# VIC20_HypExp.net
KiCad netlist of a schematic drawn in EAGLE
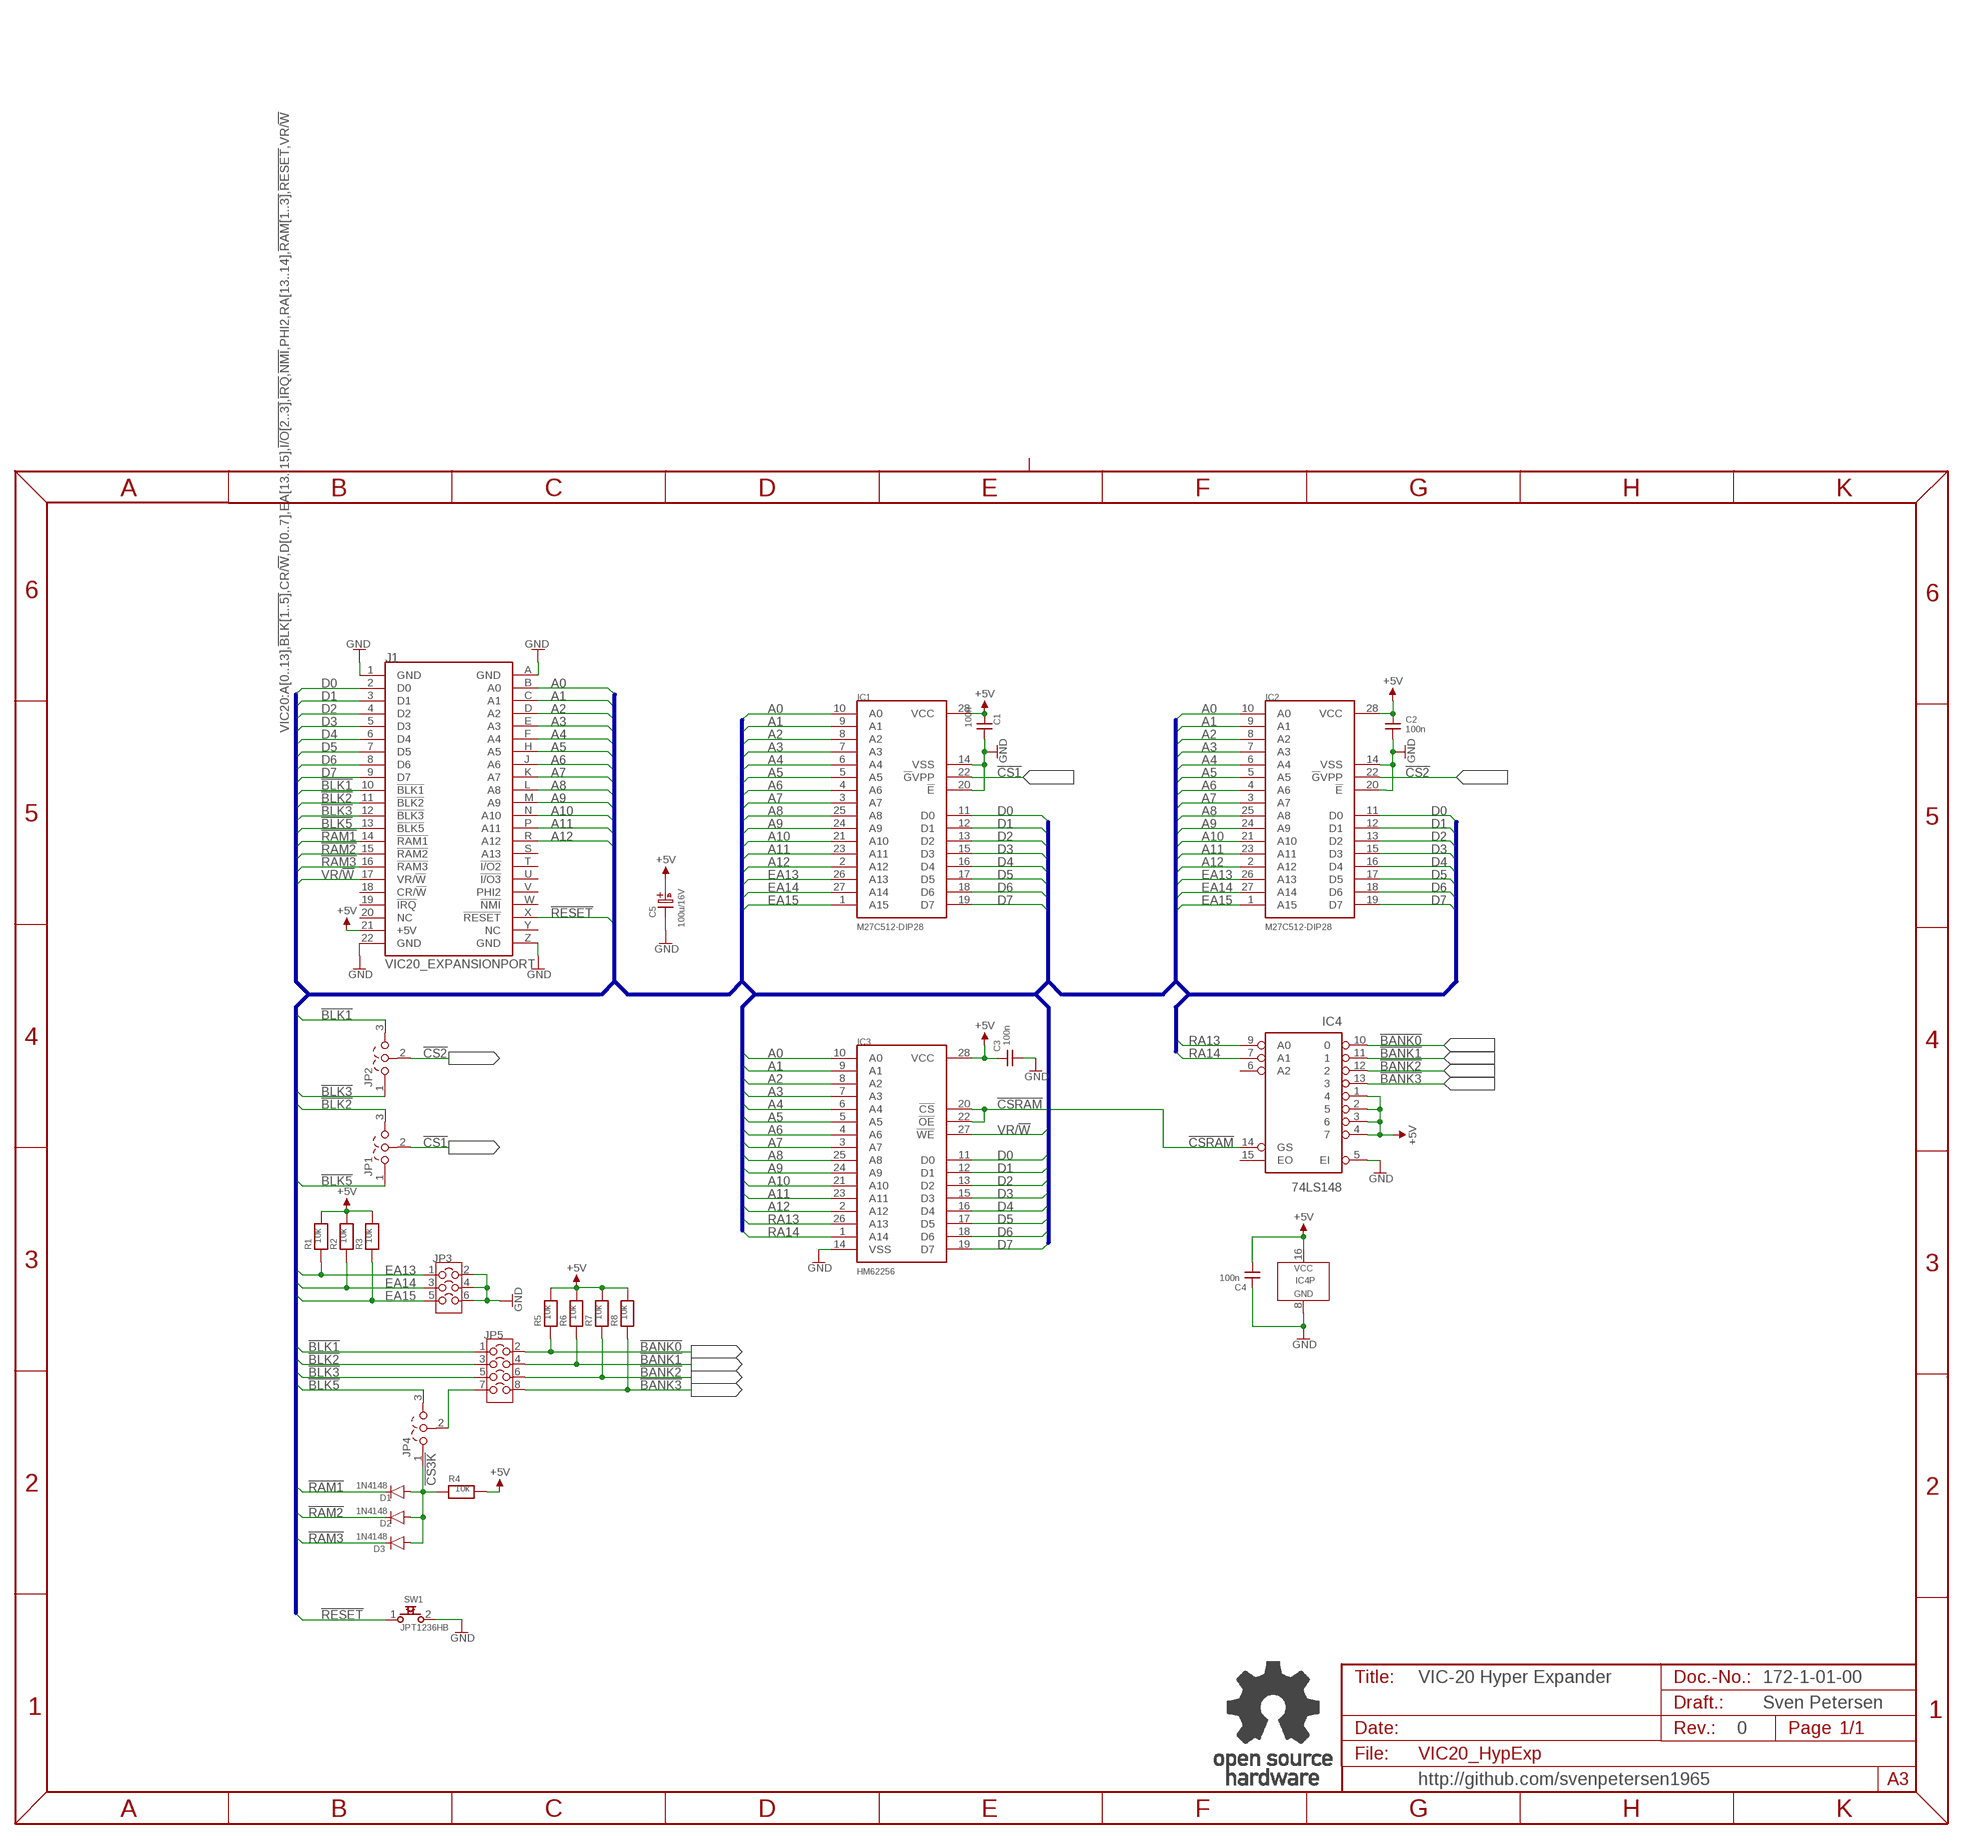
[diagram p0: schematic, sheet 1]

(export (version "E")
  (design (tool "Eeschema 10.0.6"))
  (components
    (comp (ref "C1")
      (value "100n")
      (footprint "eagle-import:C-2,5")
      (libsource (lib "eagle-import") (part "CAP01"))
    )
    (comp (ref "C2")
      (value "100n")
      (footprint "eagle-import:C-2,5")
      (libsource (lib "eagle-import") (part "CAP01"))
    )
    (comp (ref "C3")
      (value "100n")
      (footprint "eagle-import:C-2,5")
      (libsource (lib "eagle-import") (part "CAP01"))
    )
    (comp (ref "C4")
      (value "100n")
      (footprint "eagle-import:C-2,5")
      (libsource (lib "eagle-import") (part "CAP01"))
    )
    (comp (ref "C5")
      (value "100u/16V")
      (footprint "eagle-import:C07_2,5")
      (libsource (lib "eagle-import") (part "C07/2,5"))
    )
    (comp (ref "D1")
      (value "1N4148")
      (footprint "eagle-import:DO-35_3")
      (libsource (lib "eagle-import") (part "1N41480.3{dblquote}"))
    )
    (comp (ref "D2")
      (value "1N4148")
      (footprint "eagle-import:DO-35_3")
      (libsource (lib "eagle-import") (part "1N41480.3{dblquote}"))
    )
    (comp (ref "D3")
      (value "1N4148")
      (footprint "eagle-import:DO-35_3")
      (libsource (lib "eagle-import") (part "1N41480.3{dblquote}"))
    )
    (comp (ref "IC1")
      (value "M27C512-DIP28")
      (footprint "eagle-import:DIL28-6")
      (libsource (lib "eagle-import") (part "M27C512-DIP28"))
    )
    (comp (ref "IC2")
      (value "M27C512-DIP28")
      (footprint "eagle-import:DIL28-6")
      (libsource (lib "eagle-import") (part "M27C512-DIP28"))
    )
    (comp (ref "IC3")
      (value "HM62256")
      (footprint "eagle-import:DIL28-6")
      (libsource (lib "eagle-import") (part "HM62256"))
    )
    (comp (ref "IC4")
      (value "74LS148")
      (footprint "eagle-import:DIL-16")
      (libsource (lib "eagle-import") (part "74148DIL"))
    )
    (comp (ref "J1")
      (value "VIC20_EXPANSIONPORT")
      (footprint "eagle-import:VIC20_EXPANSION")
      (libsource (lib "eagle-import") (part "VIC20_EXPANSIONPORT"))
    )
    (comp (ref "JP1")
      (value "COMBI-3P")
      (footprint "eagle-import:COMBI-3P")
      (libsource (lib "eagle-import") (part "COMBI-3P"))
    )
    (comp (ref "JP2")
      (value "COMBI-3P")
      (footprint "eagle-import:COMBI-3P")
      (libsource (lib "eagle-import") (part "COMBI-3P"))
    )
    (comp (ref "JP3")
      (value "COMBI-3X2P")
      (footprint "eagle-import:COMBI-3X2")
      (libsource (lib "eagle-import") (part "COMBI-3X2P"))
    )
    (comp (ref "JP4")
      (value "COMBI-3P")
      (footprint "eagle-import:COMBI-3P")
      (libsource (lib "eagle-import") (part "COMBI-3P"))
    )
    (comp (ref "JP5")
      (value "COMBI-4X2P")
      (footprint "eagle-import:COMBI-4X2")
      (libsource (lib "eagle-import") (part "COMBI-4X2P"))
    )
    (comp (ref "R1")
      (value "10k")
      (footprint "eagle-import:R-10")
      (libsource (lib "eagle-import") (part "RES04"))
    )
    (comp (ref "R2")
      (value "10k")
      (footprint "eagle-import:R-10")
      (libsource (lib "eagle-import") (part "RES04"))
    )
    (comp (ref "R3")
      (value "10k")
      (footprint "eagle-import:R-10")
      (libsource (lib "eagle-import") (part "RES04"))
    )
    (comp (ref "R4")
      (value "10k")
      (footprint "eagle-import:R-10")
      (libsource (lib "eagle-import") (part "RES04"))
    )
    (comp (ref "R5")
      (value "10k")
      (footprint "eagle-import:R-10")
      (libsource (lib "eagle-import") (part "RES04"))
    )
    (comp (ref "R6")
      (value "10k")
      (footprint "eagle-import:R-10")
      (libsource (lib "eagle-import") (part "RES04"))
    )
    (comp (ref "R7")
      (value "10k")
      (footprint "eagle-import:R-10")
      (libsource (lib "eagle-import") (part "RES04"))
    )
    (comp (ref "R8")
      (value "10k")
      (footprint "eagle-import:R-10")
      (libsource (lib "eagle-import") (part "RES04"))
    )
    (comp (ref "SW1")
      (value "JPT1236HB")
      (footprint "eagle-import:JTP_1236HB")
      (libsource (lib "eagle-import") (part "JPT1236HB"))
    )
    (comp (ref "U$2")
      (value "OPEN_SOURCE_HW")
      (footprint "eagle-import:OPENHW")
      (libsource (lib "eagle-import") (part "OPEN_SOURCE_HW"))
    )
  )
  (nets
    (net (code "5") (name "+5V") (class "Default")
      (node (ref "C1") (pin "1") (pinfunction "1_1") (pintype "passive"))
      (node (ref "C2") (pin "1") (pinfunction "1_1") (pintype "passive"))
      (node (ref "C3") (pin "2") (pinfunction "2_2") (pintype "passive"))
      (node (ref "C4") (pin "1") (pinfunction "1_1") (pintype "passive"))
      (node (ref "C5") (pin "A") (pinfunction "+_A") (pintype "passive"))
      (node (ref "IC1") (pin "28") (pinfunction "VCC_28") (pintype "power_in"))
      (node (ref "IC2") (pin "28") (pinfunction "VCC_28") (pintype "power_in"))
      (node (ref "IC3") (pin "28") (pinfunction "VCC_28") (pintype "power_in"))
      (node (ref "IC4") (pin "1") (pinfunction "4_1") (pintype "input"))
      (node (ref "IC4") (pin "16") (pinfunction "VCC_16") (pintype "bidirectional"))
      (node (ref "IC4") (pin "2") (pinfunction "5_2") (pintype "input"))
      (node (ref "IC4") (pin "3") (pinfunction "6_3") (pintype "input"))
      (node (ref "IC4") (pin "4") (pinfunction "7_4") (pintype "input"))
      (node (ref "J1") (pin "21") (pinfunction "+5V_21") (pintype "power_in"))
      (node (ref "R1") (pin "2") (pinfunction "2_2") (pintype "passive"))
      (node (ref "R2") (pin "2") (pinfunction "2_2") (pintype "passive"))
      (node (ref "R3") (pin "2") (pinfunction "2_2") (pintype "passive"))
      (node (ref "R4") (pin "2") (pinfunction "2_2") (pintype "passive"))
      (node (ref "R5") (pin "2") (pinfunction "2_2") (pintype "passive"))
      (node (ref "R6") (pin "2") (pinfunction "2_2") (pintype "passive"))
      (node (ref "R7") (pin "2") (pinfunction "2_2") (pintype "passive"))
      (node (ref "R8") (pin "2") (pinfunction "2_2") (pintype "passive"))
    )
    (net (code "6") (name "/A0") (class "Default")
      (node (ref "IC1") (pin "10") (pinfunction "A0_10") (pintype "input"))
      (node (ref "IC2") (pin "10") (pinfunction "A0_10") (pintype "input"))
      (node (ref "IC3") (pin "10") (pinfunction "A0_10") (pintype "input"))
      (node (ref "J1") (pin "B") (pinfunction "A0_B") (pintype "bidirectional"))
    )
    (net (code "7") (name "/A1") (class "Default")
      (node (ref "IC1") (pin "9") (pinfunction "A1_9") (pintype "input"))
      (node (ref "IC2") (pin "9") (pinfunction "A1_9") (pintype "input"))
      (node (ref "IC3") (pin "9") (pinfunction "A1_9") (pintype "input"))
      (node (ref "J1") (pin "C") (pinfunction "A1_C") (pintype "bidirectional"))
    )
    (net (code "8") (name "/A2") (class "Default")
      (node (ref "IC1") (pin "8") (pinfunction "A2_8") (pintype "input"))
      (node (ref "IC2") (pin "8") (pinfunction "A2_8") (pintype "input"))
      (node (ref "IC3") (pin "8") (pinfunction "A2_8") (pintype "input"))
      (node (ref "J1") (pin "D") (pinfunction "A2_D") (pintype "bidirectional"))
    )
    (net (code "9") (name "/A3") (class "Default")
      (node (ref "IC1") (pin "7") (pinfunction "A3_7") (pintype "input"))
      (node (ref "IC2") (pin "7") (pinfunction "A3_7") (pintype "input"))
      (node (ref "IC3") (pin "7") (pinfunction "A3_7") (pintype "input"))
      (node (ref "J1") (pin "E") (pinfunction "A3_E") (pintype "bidirectional"))
    )
    (net (code "10") (name "/A4") (class "Default")
      (node (ref "IC1") (pin "6") (pinfunction "A4_6") (pintype "input"))
      (node (ref "IC2") (pin "6") (pinfunction "A4_6") (pintype "input"))
      (node (ref "IC3") (pin "6") (pinfunction "A4_6") (pintype "input"))
      (node (ref "J1") (pin "F") (pinfunction "A4_F") (pintype "bidirectional"))
    )
    (net (code "11") (name "/A5") (class "Default")
      (node (ref "IC1") (pin "5") (pinfunction "A5_5") (pintype "input"))
      (node (ref "IC2") (pin "5") (pinfunction "A5_5") (pintype "input"))
      (node (ref "IC3") (pin "5") (pinfunction "A5_5") (pintype "input"))
      (node (ref "J1") (pin "H") (pinfunction "A5_H") (pintype "bidirectional"))
    )
    (net (code "12") (name "/A6") (class "Default")
      (node (ref "IC1") (pin "4") (pinfunction "A6_4") (pintype "input"))
      (node (ref "IC2") (pin "4") (pinfunction "A6_4") (pintype "input"))
      (node (ref "IC3") (pin "4") (pinfunction "A6_4") (pintype "input"))
      (node (ref "J1") (pin "J") (pinfunction "A6_J") (pintype "bidirectional"))
    )
    (net (code "13") (name "/A7") (class "Default")
      (node (ref "IC1") (pin "3") (pinfunction "A7_3") (pintype "input"))
      (node (ref "IC2") (pin "3") (pinfunction "A7_3") (pintype "input"))
      (node (ref "IC3") (pin "3") (pinfunction "A7_3") (pintype "input"))
      (node (ref "J1") (pin "K") (pinfunction "A7_K") (pintype "bidirectional"))
    )
    (net (code "14") (name "/A8") (class "Default")
      (node (ref "IC1") (pin "25") (pinfunction "A8_25") (pintype "input"))
      (node (ref "IC2") (pin "25") (pinfunction "A8_25") (pintype "input"))
      (node (ref "IC3") (pin "25") (pinfunction "A8_25") (pintype "input"))
      (node (ref "J1") (pin "L") (pinfunction "A8_L") (pintype "bidirectional"))
    )
    (net (code "15") (name "/A9") (class "Default")
      (node (ref "IC1") (pin "24") (pinfunction "A9_24") (pintype "input"))
      (node (ref "IC2") (pin "24") (pinfunction "A9_24") (pintype "input"))
      (node (ref "IC3") (pin "24") (pinfunction "A9_24") (pintype "input"))
      (node (ref "J1") (pin "M") (pinfunction "A9_M") (pintype "bidirectional"))
    )
    (net (code "16") (name "/A10") (class "Default")
      (node (ref "IC1") (pin "21") (pinfunction "A10_21") (pintype "input"))
      (node (ref "IC2") (pin "21") (pinfunction "A10_21") (pintype "input"))
      (node (ref "IC3") (pin "21") (pinfunction "A10_21") (pintype "input"))
      (node (ref "J1") (pin "N") (pinfunction "A10_N") (pintype "bidirectional"))
    )
    (net (code "17") (name "/A11") (class "Default")
      (node (ref "IC1") (pin "23") (pinfunction "A11_23") (pintype "input"))
      (node (ref "IC2") (pin "23") (pinfunction "A11_23") (pintype "input"))
      (node (ref "IC3") (pin "23") (pinfunction "A11_23") (pintype "input"))
      (node (ref "J1") (pin "P") (pinfunction "A11_P") (pintype "bidirectional"))
    )
    (net (code "18") (name "/A12") (class "Default")
      (node (ref "IC1") (pin "2") (pinfunction "A12_2") (pintype "input"))
      (node (ref "IC2") (pin "2") (pinfunction "A12_2") (pintype "input"))
      (node (ref "IC3") (pin "2") (pinfunction "A12_2") (pintype "input"))
      (node (ref "J1") (pin "R") (pinfunction "A12_R") (pintype "bidirectional"))
    )
    (net (code "19") (name "/D0") (class "Default")
      (node (ref "IC1") (pin "11") (pinfunction "D0_11") (pintype "bidirectional"))
      (node (ref "IC2") (pin "11") (pinfunction "D0_11") (pintype "bidirectional"))
      (node (ref "IC3") (pin "11") (pinfunction "D0_11") (pintype "bidirectional"))
      (node (ref "J1") (pin "2") (pinfunction "D0_2") (pintype "bidirectional"))
    )
    (net (code "20") (name "/D1") (class "Default")
      (node (ref "IC1") (pin "12") (pinfunction "D1_12") (pintype "bidirectional"))
      (node (ref "IC2") (pin "12") (pinfunction "D1_12") (pintype "bidirectional"))
      (node (ref "IC3") (pin "12") (pinfunction "D1_12") (pintype "bidirectional"))
      (node (ref "J1") (pin "3") (pinfunction "D1_3") (pintype "bidirectional"))
    )
    (net (code "21") (name "/D2") (class "Default")
      (node (ref "IC1") (pin "13") (pinfunction "D2_13") (pintype "bidirectional"))
      (node (ref "IC2") (pin "13") (pinfunction "D2_13") (pintype "bidirectional"))
      (node (ref "IC3") (pin "13") (pinfunction "D2_13") (pintype "bidirectional"))
      (node (ref "J1") (pin "4") (pinfunction "D2_4") (pintype "bidirectional"))
    )
    (net (code "22") (name "/D3") (class "Default")
      (node (ref "IC1") (pin "15") (pinfunction "D3_15") (pintype "bidirectional"))
      (node (ref "IC2") (pin "15") (pinfunction "D3_15") (pintype "bidirectional"))
      (node (ref "IC3") (pin "15") (pinfunction "D3_15") (pintype "bidirectional"))
      (node (ref "J1") (pin "5") (pinfunction "D3_5") (pintype "bidirectional"))
    )
    (net (code "23") (name "/D4") (class "Default")
      (node (ref "IC1") (pin "16") (pinfunction "D4_16") (pintype "bidirectional"))
      (node (ref "IC2") (pin "16") (pinfunction "D4_16") (pintype "bidirectional"))
      (node (ref "IC3") (pin "16") (pinfunction "D4_16") (pintype "bidirectional"))
      (node (ref "J1") (pin "6") (pinfunction "D4_6") (pintype "bidirectional"))
    )
    (net (code "24") (name "/D5") (class "Default")
      (node (ref "IC1") (pin "17") (pinfunction "D5_17") (pintype "bidirectional"))
      (node (ref "IC2") (pin "17") (pinfunction "D5_17") (pintype "bidirectional"))
      (node (ref "IC3") (pin "17") (pinfunction "D5_17") (pintype "bidirectional"))
      (node (ref "J1") (pin "7") (pinfunction "D5_7") (pintype "bidirectional"))
    )
    (net (code "25") (name "/D6") (class "Default")
      (node (ref "IC1") (pin "18") (pinfunction "D6_18") (pintype "bidirectional"))
      (node (ref "IC2") (pin "18") (pinfunction "D6_18") (pintype "bidirectional"))
      (node (ref "IC3") (pin "18") (pinfunction "D6_18") (pintype "bidirectional"))
      (node (ref "J1") (pin "8") (pinfunction "D6_8") (pintype "bidirectional"))
    )
    (net (code "26") (name "/D7") (class "Default")
      (node (ref "IC1") (pin "19") (pinfunction "D7_19") (pintype "bidirectional"))
      (node (ref "IC2") (pin "19") (pinfunction "D7_19") (pintype "bidirectional"))
      (node (ref "IC3") (pin "19") (pinfunction "D7_19") (pintype "bidirectional"))
      (node (ref "J1") (pin "9") (pinfunction "D7_9") (pintype "bidirectional"))
    )
    (net (code "27") (name "/EA13") (class "Default")
      (node (ref "IC1") (pin "26") (pinfunction "A13_26") (pintype "input"))
      (node (ref "IC2") (pin "26") (pinfunction "A13_26") (pintype "input"))
      (node (ref "JP3") (pin "1") (pinfunction "1_1") (pintype "bidirectional"))
      (node (ref "R1") (pin "1") (pinfunction "1_1") (pintype "passive"))
    )
    (net (code "28") (name "/EA14") (class "Default")
      (node (ref "IC1") (pin "27") (pinfunction "A14_27") (pintype "input"))
      (node (ref "IC2") (pin "27") (pinfunction "A14_27") (pintype "input"))
      (node (ref "JP3") (pin "3") (pinfunction "3_3") (pintype "bidirectional"))
      (node (ref "R2") (pin "1") (pinfunction "1_1") (pintype "passive"))
    )
    (net (code "29") (name "/EA15") (class "Default")
      (node (ref "IC1") (pin "1") (pinfunction "A15_1") (pintype "input"))
      (node (ref "IC2") (pin "1") (pinfunction "A15_1") (pintype "input"))
      (node (ref "JP3") (pin "5") (pinfunction "5_5") (pintype "bidirectional"))
      (node (ref "R3") (pin "1") (pinfunction "1_1") (pintype "passive"))
    )
    (net (code "30") (name "/NC") (class "Default")
      (node (ref "J1") (pin "20") (pinfunction "NC_20") (pintype "power_in"))
    )
    (net (code "31") (name "/RA13") (class "Default")
      (node (ref "IC3") (pin "26") (pinfunction "A13_26") (pintype "input"))
      (node (ref "IC4") (pin "9") (pinfunction "A0_9") (pintype "output"))
    )
    (net (code "32") (name "/RA14") (class "Default")
      (node (ref "IC3") (pin "1") (pinfunction "A14_1") (pintype "input"))
      (node (ref "IC4") (pin "7") (pinfunction "A1_7") (pintype "output"))
    )
    (net (code "33") (name "/VR{slash}~{W}") (class "Default")
      (node (ref "IC3") (pin "27") (pinfunction "~{WE}_27") (pintype "input"))
      (node (ref "J1") (pin "17") (pinfunction "VR/~{W}_17") (pintype "output"))
    )
    (net (code "35") (name "/~{BANK0}") (class "Default")
      (node (ref "IC4") (pin "10") (pinfunction "0_10") (pintype "input"))
      (node (ref "JP5") (pin "2") (pinfunction "2_2") (pintype "bidirectional"))
      (node (ref "R5") (pin "1") (pinfunction "1_1") (pintype "passive"))
    )
    (net (code "36") (name "/~{BANK1}") (class "Default")
      (node (ref "IC4") (pin "11") (pinfunction "1_11") (pintype "input"))
      (node (ref "JP5") (pin "4") (pinfunction "4_4") (pintype "bidirectional"))
      (node (ref "R6") (pin "1") (pinfunction "1_1") (pintype "passive"))
    )
    (net (code "37") (name "/~{BANK2}") (class "Default")
      (node (ref "IC4") (pin "12") (pinfunction "2_12") (pintype "input"))
      (node (ref "JP5") (pin "6") (pinfunction "6_6") (pintype "bidirectional"))
      (node (ref "R7") (pin "1") (pinfunction "1_1") (pintype "passive"))
    )
    (net (code "38") (name "/~{BANK3}") (class "Default")
      (node (ref "IC4") (pin "13") (pinfunction "3_13") (pintype "input"))
      (node (ref "JP5") (pin "8") (pinfunction "8_8") (pintype "bidirectional"))
      (node (ref "R8") (pin "1") (pinfunction "1_1") (pintype "passive"))
    )
    (net (code "39") (name "/~{BLK1}") (class "Default")
      (node (ref "J1") (pin "10") (pinfunction "~{BLK1}_10") (pintype "input"))
      (node (ref "JP2") (pin "3") (pinfunction "3_3") (pintype "bidirectional"))
      (node (ref "JP5") (pin "1") (pinfunction "1_1") (pintype "bidirectional"))
    )
    (net (code "40") (name "/~{BLK2}") (class "Default")
      (node (ref "J1") (pin "11") (pinfunction "~{BLK2}_11") (pintype "input"))
      (node (ref "JP1") (pin "3") (pinfunction "3_3") (pintype "bidirectional"))
      (node (ref "JP5") (pin "3") (pinfunction "3_3") (pintype "bidirectional"))
    )
    (net (code "41") (name "/~{BLK3}") (class "Default")
      (node (ref "J1") (pin "12") (pinfunction "~{BLK3}_12") (pintype "output"))
      (node (ref "JP2") (pin "1") (pinfunction "1_1") (pintype "bidirectional"))
      (node (ref "JP5") (pin "5") (pinfunction "5_5") (pintype "bidirectional"))
    )
    (net (code "42") (name "/~{BLK5}") (class "Default")
      (node (ref "J1") (pin "13") (pinfunction "~{BLK5}_13") (pintype "output"))
      (node (ref "JP1") (pin "1") (pinfunction "1_1") (pintype "bidirectional"))
      (node (ref "JP4") (pin "3") (pinfunction "3_3") (pintype "bidirectional"))
    )
    (net (code "43") (name "/~{CS1}") (class "Default")
      (node (ref "IC1") (pin "22") (pinfunction "~{G}VPP_22") (pintype "input"))
      (node (ref "JP1") (pin "2") (pinfunction "2_2") (pintype "bidirectional"))
    )
    (net (code "44") (name "/~{CS2}") (class "Default")
      (node (ref "IC2") (pin "22") (pinfunction "~{G}VPP_22") (pintype "input"))
      (node (ref "JP2") (pin "2") (pinfunction "2_2") (pintype "bidirectional"))
    )
    (net (code "45") (name "/~{CS3K}") (class "Default")
      (node (ref "D1") (pin "A") (pinfunction "A_A") (pintype "passive"))
      (node (ref "D2") (pin "A") (pinfunction "A_A") (pintype "passive"))
      (node (ref "D3") (pin "A") (pinfunction "A_A") (pintype "passive"))
      (node (ref "JP4") (pin "1") (pinfunction "1_1") (pintype "bidirectional"))
      (node (ref "R4") (pin "1") (pinfunction "1_1") (pintype "passive"))
    )
    (net (code "46") (name "/~{CSRAM}") (class "Default")
      (node (ref "IC3") (pin "20") (pinfunction "~{CS}_20") (pintype "input"))
      (node (ref "IC3") (pin "22") (pinfunction "~{OE}_22") (pintype "input"))
      (node (ref "IC4") (pin "14") (pinfunction "GS_14") (pintype "output"))
    )
    (net (code "47") (name "/~{RAM1}") (class "Default")
      (node (ref "D1") (pin "K") (pinfunction "K_K") (pintype "passive"))
      (node (ref "J1") (pin "14") (pinfunction "~{RAM1}_14") (pintype "input"))
    )
    (net (code "48") (name "/~{RAM2}") (class "Default")
      (node (ref "D2") (pin "K") (pinfunction "K_K") (pintype "passive"))
      (node (ref "J1") (pin "15") (pinfunction "~{RAM2}_15") (pintype "output"))
    )
    (net (code "49") (name "/~{RAM3}") (class "Default")
      (node (ref "D3") (pin "K") (pinfunction "K_K") (pintype "passive"))
      (node (ref "J1") (pin "16") (pinfunction "~{RAM3}_16") (pintype "output"))
    )
    (net (code "50") (name "/~{RESET}") (class "Default")
      (node (ref "J1") (pin "X") (pinfunction "~{RESET}_X") (pintype "open_collector"))
      (node (ref "SW1") (pin "1") (pinfunction "1_1") (pintype "passive"))
    )
    (net (code "51") (name "GND") (class "Default")
      (node (ref "C1") (pin "2") (pinfunction "2_2") (pintype "passive"))
      (node (ref "C2") (pin "2") (pinfunction "2_2") (pintype "passive"))
      (node (ref "C3") (pin "1") (pinfunction "1_1") (pintype "passive"))
      (node (ref "C4") (pin "2") (pinfunction "2_2") (pintype "passive"))
      (node (ref "C5") (pin "K") (pinfunction "-_K") (pintype "passive"))
      (node (ref "IC1") (pin "14") (pinfunction "VSS_14") (pintype "power_in"))
      (node (ref "IC1") (pin "20") (pinfunction "~{E}_20") (pintype "input"))
      (node (ref "IC2") (pin "14") (pinfunction "VSS_14") (pintype "power_in"))
      (node (ref "IC2") (pin "20") (pinfunction "~{E}_20") (pintype "input"))
      (node (ref "IC3") (pin "14") (pinfunction "VSS_14") (pintype "power_in"))
      (node (ref "IC4") (pin "5") (pinfunction "EI_5") (pintype "input"))
      (node (ref "IC4") (pin "8") (pinfunction "GND_8") (pintype "bidirectional"))
      (node (ref "J1") (pin "1") (pinfunction "GND_1") (pintype "power_in"))
      (node (ref "J1") (pin "22") (pinfunction "GND_22") (pintype "power_in"))
      (node (ref "J1") (pin "A") (pinfunction "GND_A") (pintype "power_in"))
      (node (ref "J1") (pin "Z") (pinfunction "GND_Z") (pintype "power_in"))
      (node (ref "JP3") (pin "2") (pinfunction "2_2") (pintype "bidirectional"))
      (node (ref "JP3") (pin "4") (pinfunction "4_4") (pintype "bidirectional"))
      (node (ref "JP3") (pin "6") (pinfunction "6_6") (pintype "bidirectional"))
      (node (ref "SW1") (pin "2") (pinfunction "2_2") (pintype "passive"))
    )
    (net (code "52") (name "Net-(JP4-Pad2)") (class "Default")
      (node (ref "JP4") (pin "2") (pinfunction "2_2") (pintype "bidirectional"))
      (node (ref "JP5") (pin "7") (pinfunction "7_7") (pintype "bidirectional"))
    )
    (net (code "53") (name "unconnected-(IC4A-A2-Pad6)") (class "Default")
      (node (ref "IC4") (pin "6") (pinfunction "A2_6") (pintype "output"))
    )
    (net (code "54") (name "unconnected-(IC4A-EO-Pad15)") (class "Default")
      (node (ref "IC4") (pin "15") (pinfunction "EO_15") (pintype "output"))
    )
    (net (code "55") (name "unconnected-(J1-A13-PadS)") (class "Default")
      (node (ref "J1") (pin "S") (pinfunction "A13_S") (pintype "bidirectional"))
    )
    (net (code "56") (name "unconnected-(J1-CR{slash}~{W}-Pad18)") (class "Default")
      (node (ref "J1") (pin "18") (pinfunction "CR/~{W}_18") (pintype "output"))
    )
    (net (code "57") (name "unconnected-(J1-NC-PadY)") (class "Default")
      (node (ref "J1") (pin "Y") (pinfunction "NC_Y") (pintype "bidirectional"))
    )
    (net (code "58") (name "unconnected-(J1-PHI2-PadV)") (class "Default")
      (node (ref "J1") (pin "V") (pinfunction "PHI2_V") (pintype "bidirectional"))
    )
    (net (code "59") (name "unconnected-(J1-~{IRQ}-Pad19)") (class "Default")
      (node (ref "J1") (pin "19") (pinfunction "~{IRQ}_19") (pintype "input"))
    )
    (net (code "60") (name "unconnected-(J1-~{I{slash}O2}-PadT)") (class "Default")
      (node (ref "J1") (pin "T") (pinfunction "~{I/O2}_T") (pintype "output"))
    )
    (net (code "61") (name "unconnected-(J1-~{I{slash}O3}-PadU)") (class "Default")
      (node (ref "J1") (pin "U") (pinfunction "~{I/O3}_U") (pintype "output"))
    )
    (net (code "62") (name "unconnected-(J1-~{NMI}-PadW)") (class "Default")
      (node (ref "J1") (pin "W") (pinfunction "~{NMI}_W") (pintype "input"))
    )
  )
)
